# DS1302.net
KiCad netlist of a schematic drawn in Altium Designer
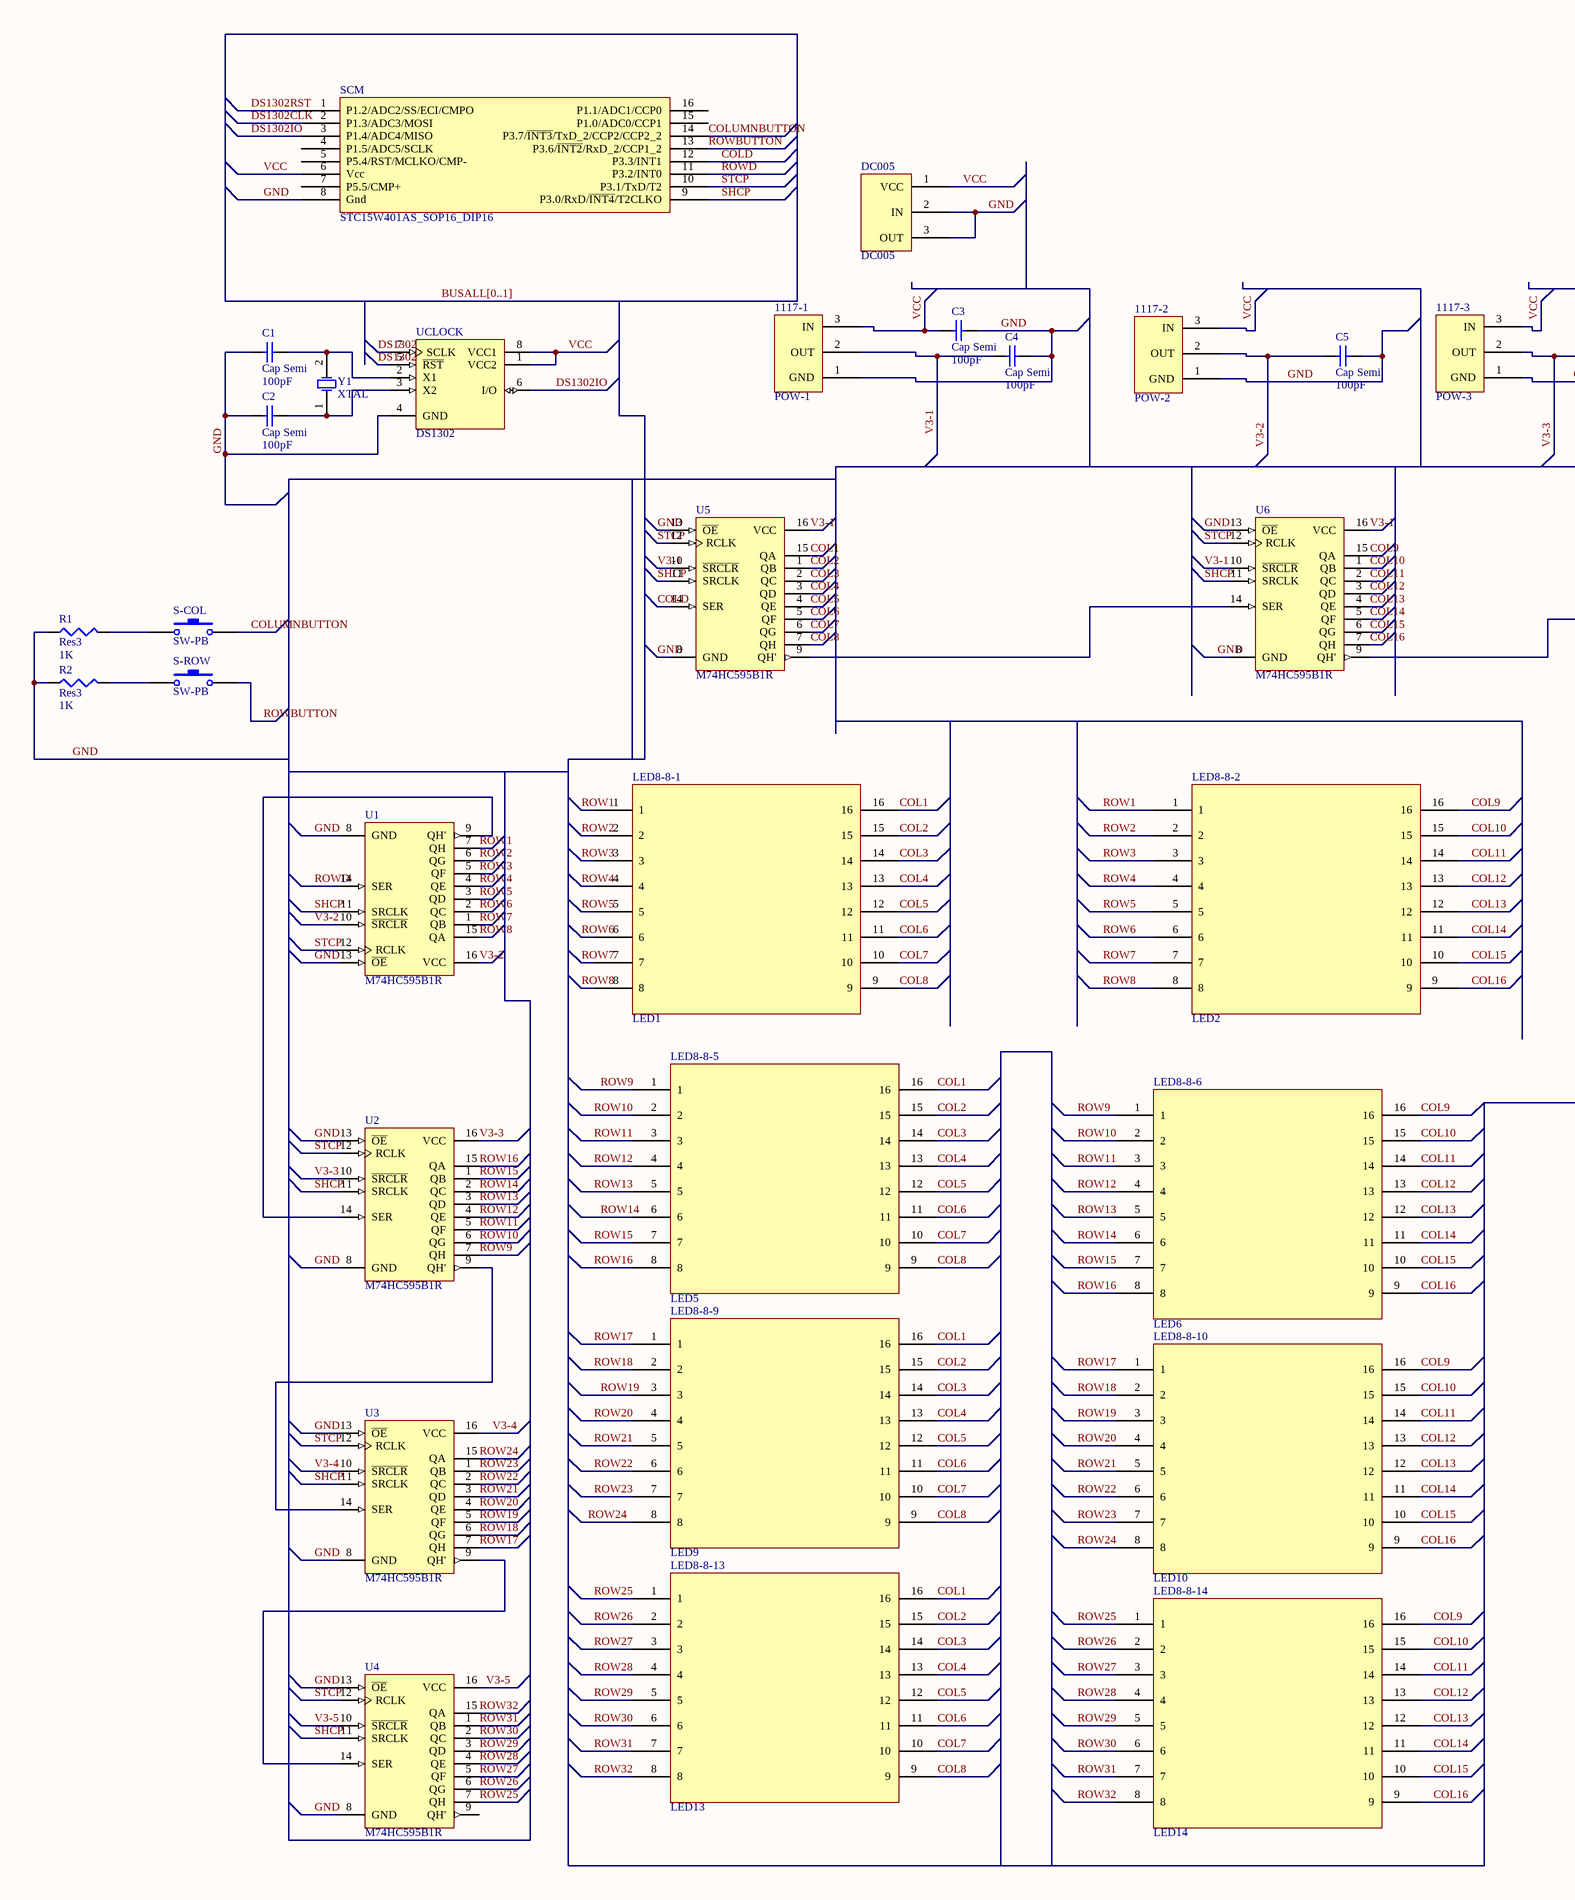
[diagram p0: DS1302.SchDoc, left]
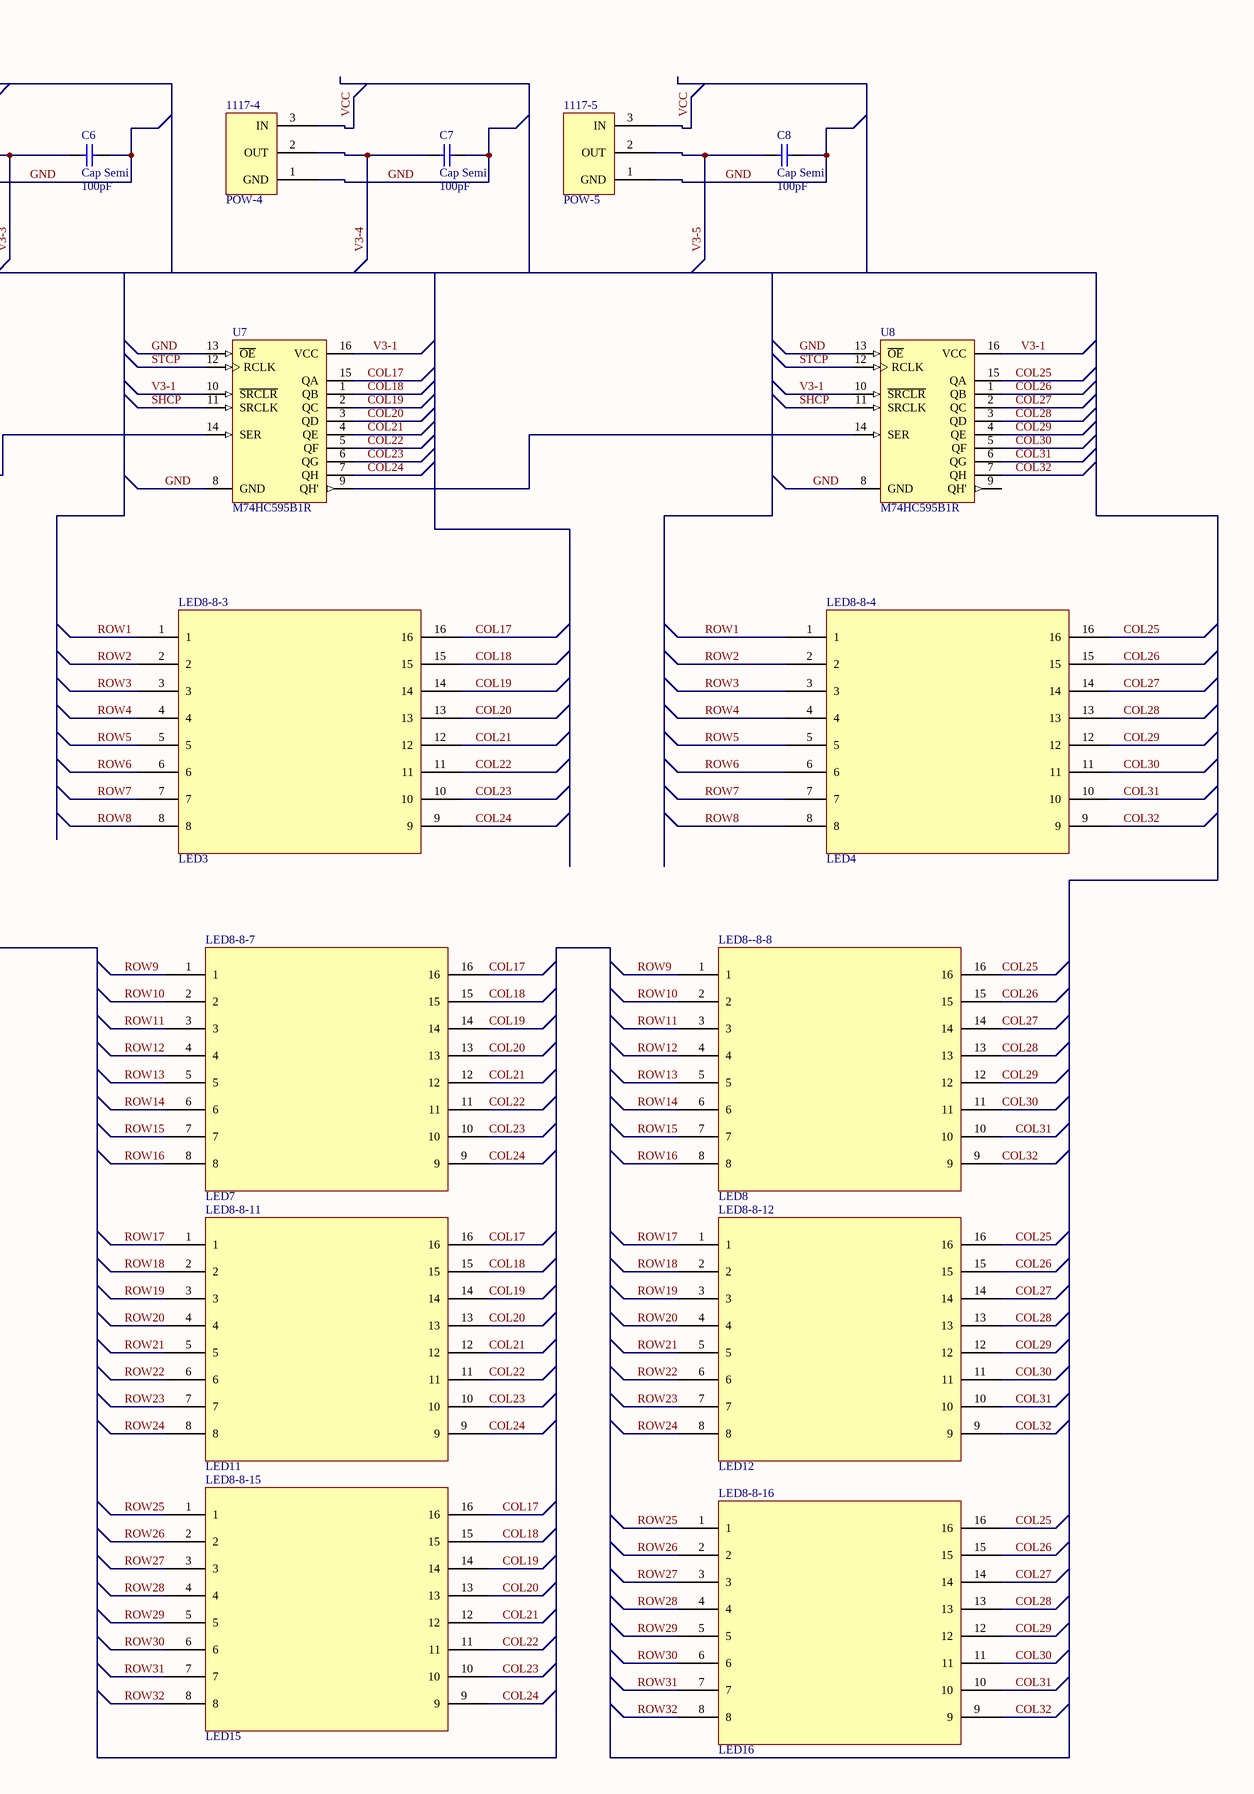
[diagram p1: DS1302.SchDoc, right]

(export (version "E")
  (design (tool "Eeschema 10.0.6"))
  (components
    (comp (ref "1117-1") (value "POW-1") (footprint "SOT223-4L") (libsource (lib "*") (part "1117")))
    (comp (ref "1117-2") (value "POW-2") (footprint "SOT223-4L") (libsource (lib "*") (part "1117")))
    (comp (ref "1117-3") (value "POW-3") (footprint "SOT223-4L") (libsource (lib "*") (part "1117")))
    (comp (ref "1117-4") (value "POW-4") (footprint "SOT223-4L") (libsource (lib "*") (part "1117")))
    (comp (ref "1117-5") (value "POW-5") (footprint "SOT223-4L") (libsource (lib "*") (part "1117")))
    (comp (ref "C1")
      (value "Cap Semi")
      (footprint "2012[0805]")
      (description "Capacitor (Semiconductor SIM Model)")
      (fields (field (name "ALTIUM_VALUE") "100pF") (field (name "PUBLISHER") "Altium Limited"))
      (libsource (lib "Miscellaneous Devices") (part "Cap Semi"))
    )
    (comp (ref "C2")
      (value "Cap Semi")
      (footprint "2012[0805]")
      (description "Capacitor (Semiconductor SIM Model)")
      (fields (field (name "ALTIUM_VALUE") "100pF") (field (name "PUBLISHER") "Altium Limited"))
      (libsource (lib "Miscellaneous Devices") (part "Cap Semi"))
    )
    (comp (ref "C3")
      (value "Cap Semi")
      (footprint "2012[0805]")
      (description "Capacitor (Semiconductor SIM Model)")
      (fields (field (name "ALTIUM_VALUE") "100pF") (field (name "PUBLISHER") "Altium Limited"))
      (libsource (lib "Miscellaneous Devices") (part "Cap Semi"))
    )
    (comp (ref "C4")
      (value "Cap Semi")
      (footprint "2012[0805]")
      (description "Capacitor (Semiconductor SIM Model)")
      (fields (field (name "ALTIUM_VALUE") "100pF") (field (name "PUBLISHER") "Altium Limited"))
      (libsource (lib "Miscellaneous Devices") (part "Cap Semi"))
    )
    (comp (ref "C5")
      (value "Cap Semi")
      (footprint "2012[0805]")
      (description "Capacitor (Semiconductor SIM Model)")
      (fields (field (name "ALTIUM_VALUE") "100pF") (field (name "PUBLISHER") "Altium Limited"))
      (libsource (lib "Miscellaneous Devices") (part "Cap Semi"))
    )
    (comp (ref "C6")
      (value "Cap Semi")
      (footprint "2012[0805]")
      (description "Capacitor (Semiconductor SIM Model)")
      (fields (field (name "ALTIUM_VALUE") "100pF") (field (name "PUBLISHER") "Altium Limited"))
      (libsource (lib "Miscellaneous Devices") (part "Cap Semi"))
    )
    (comp (ref "C7")
      (value "Cap Semi")
      (footprint "2012[0805]")
      (description "Capacitor (Semiconductor SIM Model)")
      (fields (field (name "ALTIUM_VALUE") "100pF") (field (name "PUBLISHER") "Altium Limited"))
      (libsource (lib "Miscellaneous Devices") (part "Cap Semi"))
    )
    (comp (ref "C8")
      (value "Cap Semi")
      (footprint "2012[0805]")
      (description "Capacitor (Semiconductor SIM Model)")
      (fields (field (name "ALTIUM_VALUE") "100pF") (field (name "PUBLISHER") "Altium Limited"))
      (libsource (lib "Miscellaneous Devices") (part "Cap Semi"))
    )
    (comp (ref "DC005") (value "DC005") (footprint "DC005") (libsource (lib "*") (part "DC005")))
    (comp (ref "LED8--8-8")
      (value "LED8")
      (footprint "LED8-8New")
      (libsource (lib "Schlib1") (part "LED8-8"))
    )
    (comp (ref "LED8-8-1") (value "LED1") (footprint "LED8-8New") (libsource (lib "Schlib1") (part "LED8-8")))
    (comp (ref "LED8-8-2") (value "LED2") (footprint "LED8-8New") (libsource (lib "") (part "LED8-8_1")))
    (comp (ref "LED8-8-3") (value "LED3") (footprint "LED8-8New") (libsource (lib "") (part "LED8-8_1")))
    (comp (ref "LED8-8-4") (value "LED4") (footprint "LED8-8New") (libsource (lib "") (part "LED8-8_1")))
    (comp (ref "LED8-8-5") (value "LED5") (footprint "LED8-8New") (libsource (lib "Schlib1") (part "LED8-8")))
    (comp (ref "LED8-8-6") (value "LED6") (footprint "LED8-8New") (libsource (lib "Schlib1") (part "LED8-8")))
    (comp (ref "LED8-8-7") (value "LED7") (footprint "LED8-8New") (libsource (lib "Schlib1") (part "LED8-8")))
    (comp (ref "LED8-8-9") (value "LED9") (footprint "LED8-8New") (libsource (lib "Schlib1") (part "LED8-8")))
    (comp (ref "LED8-8-10")
      (value "LED10")
      (footprint "LED8-8New")
      (libsource (lib "Schlib1") (part "LED8-8"))
    )
    (comp (ref "LED8-8-11")
      (value "LED11")
      (footprint "LED8-8New")
      (libsource (lib "Schlib1") (part "LED8-8"))
    )
    (comp (ref "LED8-8-12")
      (value "LED12")
      (footprint "LED8-8New")
      (libsource (lib "Schlib1") (part "LED8-8"))
    )
    (comp (ref "LED8-8-13") (value "LED13") (footprint "LED8-8New") (libsource (lib "") (part "LED8-8_1")))
    (comp (ref "LED8-8-14") (value "LED14") (footprint "LED8-8New") (libsource (lib "*") (part "LED8-8")))
    (comp (ref "LED8-8-15") (value "LED15") (footprint "LED8-8New") (libsource (lib "*") (part "LED8-8")))
    (comp (ref "LED8-8-16") (value "LED16") (footprint "LED8-8New") (libsource (lib "*") (part "LED8-8")))
    (comp (ref "R1")
      (value "Res3")
      (footprint "2012[0805]")
      (description "Resistor")
      (fields (field (name "ALTIUM_VALUE") "1K") (field (name "PUBLISHER") "Altium Limited"))
      (libsource (lib "Miscellaneous Devices") (part "Res3"))
    )
    (comp (ref "R2")
      (value "Res3")
      (footprint "2012[0805]")
      (description "Resistor")
      (fields (field (name "ALTIUM_VALUE") "1K") (field (name "PUBLISHER") "Altium Limited"))
      (libsource (lib "Miscellaneous Devices") (part "Res3"))
    )
    (comp (ref "S-COL")
      (value "SW-PB")
      (footprint "6332[2512]")
      (description "Switch")
      (fields (field (name "PUBLISHER") "Altium Limited"))
      (libsource (lib "Miscellaneous Devices") (part "SW-PB"))
    )
    (comp (ref "S-ROW")
      (value "SW-PB")
      (footprint "6332[2512]")
      (description "Switch")
      (fields (field (name "PUBLISHER") "Altium Limited"))
      (libsource (lib "Miscellaneous Devices") (part "SW-PB"))
    )
    (comp (ref "SCM")
      (value "STC15W401AS_SOP16_DIP16")
      (footprint "DIP-16")
      (libsource (lib "stcmcu_Protel99_sch") (part "STC15W401AS_SOP16_DIP16"))
    )
    (comp (ref "U1")
      (value "M74HC595B1R")
      (footprint "DIP-16")
      (description "8 Bit Shift Register with Output Latches (3 STATE)")
      (fields (field (name "PUBLISHER") "Altium Limited"))
      (libsource (lib "") (part "M74HC595B1R_1"))
    )
    (comp (ref "U2")
      (value "M74HC595B1R")
      (footprint "DIP-16")
      (description "8 Bit Shift Register with Output Latches (3 STATE)")
      (fields (field (name "PUBLISHER") "Altium Limited"))
      (libsource (lib "ST Logic Register") (part "M74HC595B1R"))
    )
    (comp (ref "U3")
      (value "M74HC595B1R")
      (footprint "DIP-16")
      (description "8 Bit Shift Register with Output Latches (3 STATE)")
      (fields (field (name "PUBLISHER") "Altium Limited"))
      (libsource (lib "ST Logic Register") (part "M74HC595B1R"))
    )
    (comp (ref "U4")
      (value "M74HC595B1R")
      (footprint "DIP-16")
      (description "8 Bit Shift Register with Output Latches (3 STATE)")
      (fields (field (name "PUBLISHER") "Altium Limited"))
      (libsource (lib "ST Logic Register") (part "M74HC595B1R"))
    )
    (comp (ref "U5")
      (value "M74HC595B1R")
      (footprint "DIP-16")
      (description "8 Bit Shift Register with Output Latches (3 STATE)")
      (fields (field (name "PUBLISHER") "Altium Limited"))
      (libsource (lib "ST Logic Register") (part "M74HC595B1R"))
    )
    (comp (ref "U6")
      (value "M74HC595B1R")
      (footprint "DIP-16")
      (description "8 Bit Shift Register with Output Latches (3 STATE)")
      (fields (field (name "PUBLISHER") "Altium Limited"))
      (libsource (lib "ST Logic Register") (part "M74HC595B1R"))
    )
    (comp (ref "U7")
      (value "M74HC595B1R")
      (footprint "DIP-16")
      (description "8 Bit Shift Register with Output Latches (3 STATE)")
      (fields (field (name "PUBLISHER") "Altium Limited"))
      (libsource (lib "ST Logic Register") (part "M74HC595B1R"))
    )
    (comp (ref "U8")
      (value "M74HC595B1R")
      (footprint "DIP-16")
      (description "8 Bit Shift Register with Output Latches (3 STATE)")
      (fields (field (name "PUBLISHER") "Altium Limited"))
      (libsource (lib "ST Logic Register") (part "M74HC595B1R"))
    )
    (comp (ref "UCLOCK")
      (value "DS1302")
      (footprint "DIP8")
      (description "Trickle Charge Timekeeping Chip")
      (fields (field (name "PUBLISHER") "Altium Limited"))
      (libsource (lib "Dallas Peripheral Real Time Clock") (part "DS1302"))
    )
    (comp (ref "Y1")
      (value "XTAL")
      (footprint "R38")
      (description "Crystal Oscillator")
      (fields (field (name "PUBLISHER") "Altium Limited"))
      (libsource (lib "Miscellaneous Devices") (part "XTAL"))
    )
  )
  (nets
    (net (code "4") (name "/COL1") (class "Default")
      (node (ref "LED8-8-1") (pin "16") (pinfunction "16_16") (pintype "passive"))
      (node (ref "LED8-8-13") (pin "16") (pinfunction "16_16") (pintype "passive"))
      (node (ref "LED8-8-5") (pin "16") (pinfunction "16_16") (pintype "passive"))
      (node (ref "LED8-8-9") (pin "16") (pinfunction "16_16") (pintype "passive"))
      (node (ref "U5") (pin "15") (pinfunction "QA_15") (pintype "tri_state"))
    )
    (net (code "5") (name "/COL2") (class "Default")
      (node (ref "LED8-8-1") (pin "15") (pinfunction "15_15") (pintype "passive"))
      (node (ref "LED8-8-13") (pin "15") (pinfunction "15_15") (pintype "passive"))
      (node (ref "LED8-8-5") (pin "15") (pinfunction "15_15") (pintype "passive"))
      (node (ref "LED8-8-9") (pin "15") (pinfunction "15_15") (pintype "passive"))
      (node (ref "U5") (pin "1") (pinfunction "QB_1") (pintype "tri_state"))
    )
    (net (code "6") (name "/COL3") (class "Default")
      (node (ref "LED8-8-1") (pin "14") (pinfunction "14_14") (pintype "passive"))
      (node (ref "LED8-8-13") (pin "14") (pinfunction "14_14") (pintype "passive"))
      (node (ref "LED8-8-5") (pin "14") (pinfunction "14_14") (pintype "passive"))
      (node (ref "LED8-8-9") (pin "14") (pinfunction "14_14") (pintype "passive"))
      (node (ref "U5") (pin "2") (pinfunction "QC_2") (pintype "tri_state"))
    )
    (net (code "7") (name "/COL4") (class "Default")
      (node (ref "LED8-8-1") (pin "13") (pinfunction "13_13") (pintype "passive"))
      (node (ref "LED8-8-13") (pin "13") (pinfunction "13_13") (pintype "passive"))
      (node (ref "LED8-8-5") (pin "13") (pinfunction "13_13") (pintype "passive"))
      (node (ref "LED8-8-9") (pin "13") (pinfunction "13_13") (pintype "passive"))
      (node (ref "U5") (pin "3") (pinfunction "QD_3") (pintype "tri_state"))
    )
    (net (code "8") (name "/COL5") (class "Default")
      (node (ref "LED8-8-1") (pin "12") (pinfunction "12_12") (pintype "passive"))
      (node (ref "LED8-8-13") (pin "12") (pinfunction "12_12") (pintype "passive"))
      (node (ref "LED8-8-5") (pin "12") (pinfunction "12_12") (pintype "passive"))
      (node (ref "LED8-8-9") (pin "12") (pinfunction "12_12") (pintype "passive"))
      (node (ref "U5") (pin "4") (pinfunction "QE_4") (pintype "tri_state"))
    )
    (net (code "9") (name "/COL6") (class "Default")
      (node (ref "LED8-8-1") (pin "11") (pinfunction "11_11") (pintype "passive"))
      (node (ref "LED8-8-13") (pin "11") (pinfunction "11_11") (pintype "passive"))
      (node (ref "LED8-8-5") (pin "11") (pinfunction "11_11") (pintype "passive"))
      (node (ref "LED8-8-9") (pin "11") (pinfunction "11_11") (pintype "passive"))
      (node (ref "U5") (pin "5") (pinfunction "QF_5") (pintype "tri_state"))
    )
    (net (code "10") (name "/COL7") (class "Default")
      (node (ref "LED8-8-1") (pin "10") (pinfunction "10_10") (pintype "passive"))
      (node (ref "LED8-8-13") (pin "10") (pinfunction "10_10") (pintype "passive"))
      (node (ref "LED8-8-5") (pin "10") (pinfunction "10_10") (pintype "passive"))
      (node (ref "LED8-8-9") (pin "10") (pinfunction "10_10") (pintype "passive"))
      (node (ref "U5") (pin "6") (pinfunction "QG_6") (pintype "tri_state"))
    )
    (net (code "11") (name "/COL8") (class "Default")
      (node (ref "LED8-8-1") (pin "9") (pinfunction "9_9") (pintype "passive"))
      (node (ref "LED8-8-13") (pin "9") (pinfunction "9_9") (pintype "passive"))
      (node (ref "LED8-8-5") (pin "9") (pinfunction "9_9") (pintype "passive"))
      (node (ref "LED8-8-9") (pin "9") (pinfunction "9_9") (pintype "passive"))
      (node (ref "U5") (pin "7") (pinfunction "QH_7") (pintype "tri_state"))
    )
    (net (code "12") (name "/COL9") (class "Default")
      (node (ref "LED8-8-10") (pin "16") (pinfunction "16_16") (pintype "passive"))
      (node (ref "LED8-8-14") (pin "16") (pinfunction "16_16") (pintype "passive"))
      (node (ref "LED8-8-2") (pin "16") (pinfunction "16_16") (pintype "passive"))
      (node (ref "LED8-8-6") (pin "16") (pinfunction "16_16") (pintype "passive"))
      (node (ref "U6") (pin "15") (pinfunction "QA_15") (pintype "tri_state"))
    )
    (net (code "13") (name "/COL10") (class "Default")
      (node (ref "LED8-8-10") (pin "15") (pinfunction "15_15") (pintype "passive"))
      (node (ref "LED8-8-14") (pin "15") (pinfunction "15_15") (pintype "passive"))
      (node (ref "LED8-8-2") (pin "15") (pinfunction "15_15") (pintype "passive"))
      (node (ref "LED8-8-6") (pin "15") (pinfunction "15_15") (pintype "passive"))
      (node (ref "U6") (pin "1") (pinfunction "QB_1") (pintype "tri_state"))
    )
    (net (code "14") (name "/COL11") (class "Default")
      (node (ref "LED8-8-10") (pin "14") (pinfunction "14_14") (pintype "passive"))
      (node (ref "LED8-8-14") (pin "14") (pinfunction "14_14") (pintype "passive"))
      (node (ref "LED8-8-2") (pin "14") (pinfunction "14_14") (pintype "passive"))
      (node (ref "LED8-8-6") (pin "14") (pinfunction "14_14") (pintype "passive"))
      (node (ref "U6") (pin "2") (pinfunction "QC_2") (pintype "tri_state"))
    )
    (net (code "15") (name "/COL12") (class "Default")
      (node (ref "LED8-8-10") (pin "13") (pinfunction "13_13") (pintype "passive"))
      (node (ref "LED8-8-14") (pin "13") (pinfunction "13_13") (pintype "passive"))
      (node (ref "LED8-8-2") (pin "13") (pinfunction "13_13") (pintype "passive"))
      (node (ref "LED8-8-6") (pin "13") (pinfunction "13_13") (pintype "passive"))
      (node (ref "U6") (pin "3") (pinfunction "QD_3") (pintype "tri_state"))
    )
    (net (code "16") (name "/COL13") (class "Default")
      (node (ref "LED8-8-10") (pin "12") (pinfunction "12_12") (pintype "passive"))
      (node (ref "LED8-8-14") (pin "12") (pinfunction "12_12") (pintype "passive"))
      (node (ref "LED8-8-2") (pin "12") (pinfunction "12_12") (pintype "passive"))
      (node (ref "LED8-8-6") (pin "12") (pinfunction "12_12") (pintype "passive"))
      (node (ref "U6") (pin "4") (pinfunction "QE_4") (pintype "tri_state"))
    )
    (net (code "17") (name "/COL14") (class "Default")
      (node (ref "LED8-8-10") (pin "11") (pinfunction "11_11") (pintype "passive"))
      (node (ref "LED8-8-14") (pin "11") (pinfunction "11_11") (pintype "passive"))
      (node (ref "LED8-8-2") (pin "11") (pinfunction "11_11") (pintype "passive"))
      (node (ref "LED8-8-6") (pin "11") (pinfunction "11_11") (pintype "passive"))
      (node (ref "U6") (pin "5") (pinfunction "QF_5") (pintype "tri_state"))
    )
    (net (code "18") (name "/COL15") (class "Default")
      (node (ref "LED8-8-10") (pin "10") (pinfunction "10_10") (pintype "passive"))
      (node (ref "LED8-8-14") (pin "10") (pinfunction "10_10") (pintype "passive"))
      (node (ref "LED8-8-2") (pin "10") (pinfunction "10_10") (pintype "passive"))
      (node (ref "LED8-8-6") (pin "10") (pinfunction "10_10") (pintype "passive"))
      (node (ref "U6") (pin "6") (pinfunction "QG_6") (pintype "tri_state"))
    )
    (net (code "19") (name "/COL16") (class "Default")
      (node (ref "LED8-8-10") (pin "9") (pinfunction "9_9") (pintype "passive"))
      (node (ref "LED8-8-14") (pin "9") (pinfunction "9_9") (pintype "passive"))
      (node (ref "LED8-8-2") (pin "9") (pinfunction "9_9") (pintype "passive"))
      (node (ref "LED8-8-6") (pin "9") (pinfunction "9_9") (pintype "passive"))
      (node (ref "U6") (pin "7") (pinfunction "QH_7") (pintype "tri_state"))
    )
    (net (code "20") (name "/COL17") (class "Default")
      (node (ref "LED8-8-11") (pin "16") (pinfunction "16_16") (pintype "passive"))
      (node (ref "LED8-8-15") (pin "16") (pinfunction "16_16") (pintype "passive"))
      (node (ref "LED8-8-3") (pin "16") (pinfunction "16_16") (pintype "passive"))
      (node (ref "LED8-8-7") (pin "16") (pinfunction "16_16") (pintype "passive"))
      (node (ref "U7") (pin "15") (pinfunction "QA_15") (pintype "tri_state"))
    )
    (net (code "21") (name "/COL18") (class "Default")
      (node (ref "LED8-8-11") (pin "15") (pinfunction "15_15") (pintype "passive"))
      (node (ref "LED8-8-15") (pin "15") (pinfunction "15_15") (pintype "passive"))
      (node (ref "LED8-8-3") (pin "15") (pinfunction "15_15") (pintype "passive"))
      (node (ref "LED8-8-7") (pin "15") (pinfunction "15_15") (pintype "passive"))
      (node (ref "U7") (pin "1") (pinfunction "QB_1") (pintype "tri_state"))
    )
    (net (code "22") (name "/COL19") (class "Default")
      (node (ref "LED8-8-11") (pin "14") (pinfunction "14_14") (pintype "passive"))
      (node (ref "LED8-8-15") (pin "14") (pinfunction "14_14") (pintype "passive"))
      (node (ref "LED8-8-3") (pin "14") (pinfunction "14_14") (pintype "passive"))
      (node (ref "LED8-8-7") (pin "14") (pinfunction "14_14") (pintype "passive"))
      (node (ref "U7") (pin "2") (pinfunction "QC_2") (pintype "tri_state"))
    )
    (net (code "23") (name "/COL20") (class "Default")
      (node (ref "LED8-8-11") (pin "13") (pinfunction "13_13") (pintype "passive"))
      (node (ref "LED8-8-15") (pin "13") (pinfunction "13_13") (pintype "passive"))
      (node (ref "LED8-8-3") (pin "13") (pinfunction "13_13") (pintype "passive"))
      (node (ref "LED8-8-7") (pin "13") (pinfunction "13_13") (pintype "passive"))
      (node (ref "U7") (pin "3") (pinfunction "QD_3") (pintype "tri_state"))
    )
    (net (code "24") (name "/COL21") (class "Default")
      (node (ref "LED8-8-11") (pin "12") (pinfunction "12_12") (pintype "passive"))
      (node (ref "LED8-8-15") (pin "12") (pinfunction "12_12") (pintype "passive"))
      (node (ref "LED8-8-3") (pin "12") (pinfunction "12_12") (pintype "passive"))
      (node (ref "LED8-8-7") (pin "12") (pinfunction "12_12") (pintype "passive"))
      (node (ref "U7") (pin "4") (pinfunction "QE_4") (pintype "tri_state"))
    )
    (net (code "25") (name "/COL22") (class "Default")
      (node (ref "LED8-8-11") (pin "11") (pinfunction "11_11") (pintype "passive"))
      (node (ref "LED8-8-15") (pin "11") (pinfunction "11_11") (pintype "passive"))
      (node (ref "LED8-8-3") (pin "11") (pinfunction "11_11") (pintype "passive"))
      (node (ref "LED8-8-7") (pin "11") (pinfunction "11_11") (pintype "passive"))
      (node (ref "U7") (pin "5") (pinfunction "QF_5") (pintype "tri_state"))
    )
    (net (code "26") (name "/COL23") (class "Default")
      (node (ref "LED8-8-11") (pin "10") (pinfunction "10_10") (pintype "passive"))
      (node (ref "LED8-8-15") (pin "10") (pinfunction "10_10") (pintype "passive"))
      (node (ref "LED8-8-3") (pin "10") (pinfunction "10_10") (pintype "passive"))
      (node (ref "LED8-8-7") (pin "10") (pinfunction "10_10") (pintype "passive"))
      (node (ref "U7") (pin "6") (pinfunction "QG_6") (pintype "tri_state"))
    )
    (net (code "27") (name "/COL24") (class "Default")
      (node (ref "LED8-8-11") (pin "9") (pinfunction "9_9") (pintype "passive"))
      (node (ref "LED8-8-15") (pin "9") (pinfunction "9_9") (pintype "passive"))
      (node (ref "LED8-8-3") (pin "9") (pinfunction "9_9") (pintype "passive"))
      (node (ref "LED8-8-7") (pin "9") (pinfunction "9_9") (pintype "passive"))
      (node (ref "U7") (pin "7") (pinfunction "QH_7") (pintype "tri_state"))
    )
    (net (code "28") (name "/COL25") (class "Default")
      (node (ref "LED8--8-8") (pin "16") (pinfunction "16_16") (pintype "passive"))
      (node (ref "LED8-8-12") (pin "16") (pinfunction "16_16") (pintype "passive"))
      (node (ref "LED8-8-16") (pin "16") (pinfunction "16_16") (pintype "passive"))
      (node (ref "LED8-8-4") (pin "16") (pinfunction "16_16") (pintype "passive"))
      (node (ref "U8") (pin "15") (pinfunction "QA_15") (pintype "tri_state"))
    )
    (net (code "29") (name "/COL26") (class "Default")
      (node (ref "LED8--8-8") (pin "15") (pinfunction "15_15") (pintype "passive"))
      (node (ref "LED8-8-12") (pin "15") (pinfunction "15_15") (pintype "passive"))
      (node (ref "LED8-8-16") (pin "15") (pinfunction "15_15") (pintype "passive"))
      (node (ref "LED8-8-4") (pin "15") (pinfunction "15_15") (pintype "passive"))
      (node (ref "U8") (pin "1") (pinfunction "QB_1") (pintype "tri_state"))
    )
    (net (code "30") (name "/COL27") (class "Default")
      (node (ref "LED8--8-8") (pin "14") (pinfunction "14_14") (pintype "passive"))
      (node (ref "LED8-8-12") (pin "14") (pinfunction "14_14") (pintype "passive"))
      (node (ref "LED8-8-16") (pin "14") (pinfunction "14_14") (pintype "passive"))
      (node (ref "LED8-8-4") (pin "14") (pinfunction "14_14") (pintype "passive"))
      (node (ref "U8") (pin "2") (pinfunction "QC_2") (pintype "tri_state"))
    )
    (net (code "31") (name "/COL28") (class "Default")
      (node (ref "LED8--8-8") (pin "13") (pinfunction "13_13") (pintype "passive"))
      (node (ref "LED8-8-12") (pin "13") (pinfunction "13_13") (pintype "passive"))
      (node (ref "LED8-8-16") (pin "13") (pinfunction "13_13") (pintype "passive"))
      (node (ref "LED8-8-4") (pin "13") (pinfunction "13_13") (pintype "passive"))
      (node (ref "U8") (pin "3") (pinfunction "QD_3") (pintype "tri_state"))
    )
    (net (code "32") (name "/COL29") (class "Default")
      (node (ref "LED8--8-8") (pin "12") (pinfunction "12_12") (pintype "passive"))
      (node (ref "LED8-8-12") (pin "12") (pinfunction "12_12") (pintype "passive"))
      (node (ref "LED8-8-16") (pin "12") (pinfunction "12_12") (pintype "passive"))
      (node (ref "LED8-8-4") (pin "12") (pinfunction "12_12") (pintype "passive"))
      (node (ref "U8") (pin "4") (pinfunction "QE_4") (pintype "tri_state"))
    )
    (net (code "33") (name "/COL30") (class "Default")
      (node (ref "LED8--8-8") (pin "11") (pinfunction "11_11") (pintype "passive"))
      (node (ref "LED8-8-12") (pin "11") (pinfunction "11_11") (pintype "passive"))
      (node (ref "LED8-8-16") (pin "11") (pinfunction "11_11") (pintype "passive"))
      (node (ref "LED8-8-4") (pin "11") (pinfunction "11_11") (pintype "passive"))
      (node (ref "U8") (pin "5") (pinfunction "QF_5") (pintype "tri_state"))
    )
    (net (code "34") (name "/COL31") (class "Default")
      (node (ref "LED8--8-8") (pin "10") (pinfunction "10_10") (pintype "passive"))
      (node (ref "LED8-8-12") (pin "10") (pinfunction "10_10") (pintype "passive"))
      (node (ref "LED8-8-16") (pin "10") (pinfunction "10_10") (pintype "passive"))
      (node (ref "LED8-8-4") (pin "10") (pinfunction "10_10") (pintype "passive"))
      (node (ref "U8") (pin "6") (pinfunction "QG_6") (pintype "tri_state"))
    )
    (net (code "35") (name "/COL32") (class "Default")
      (node (ref "LED8--8-8") (pin "9") (pinfunction "9_9") (pintype "passive"))
      (node (ref "LED8-8-12") (pin "9") (pinfunction "9_9") (pintype "passive"))
      (node (ref "LED8-8-16") (pin "9") (pinfunction "9_9") (pintype "passive"))
      (node (ref "LED8-8-4") (pin "9") (pinfunction "9_9") (pintype "passive"))
      (node (ref "U8") (pin "7") (pinfunction "QH_7") (pintype "tri_state"))
    )
    (net (code "36") (name "/COLD") (class "Default")
      (node (ref "SCM") (pin "12") (pinfunction "P3.3/INT1_12") (pintype "passive"))
      (node (ref "U5") (pin "14") (pinfunction "SER_14") (pintype "input"))
    )
    (net (code "37") (name "/COLUMNBUTTON") (class "Default")
      (node (ref "S-COL") (pin "2") (pinfunction "2_2") (pintype "passive"))
      (node (ref "SCM") (pin "14") (pinfunction "P3.7/~{INT3}/TxD_2/CCP2/CCP2_2_14") (pintype "passive"))
    )
    (net (code "38") (name "/DS1302CLK") (class "Default")
      (node (ref "SCM") (pin "2") (pinfunction "P1.3/ADC3/MOSI_2") (pintype "passive"))
      (node (ref "UCLOCK") (pin "7") (pinfunction "SCLK_7") (pintype "input"))
    )
    (net (code "39") (name "/DS1302IO") (class "Default")
      (node (ref "SCM") (pin "3") (pinfunction "P1.4/ADC4/MISO_3") (pintype "passive"))
      (node (ref "UCLOCK") (pin "6") (pinfunction "I/O_6") (pintype "bidirectional"))
    )
    (net (code "40") (name "/DS1302RST") (class "Default")
      (node (ref "SCM") (pin "1") (pinfunction "P1.2/ADC2/SS/ECI/CMPO_1") (pintype "passive"))
      (node (ref "UCLOCK") (pin "5") (pinfunction "~{RST}_5") (pintype "input"))
    )
    (net (code "41") (name "/GND") (class "Default")
      (node (ref "1117-1") (pin "1") (pinfunction "GND_1") (pintype "passive"))
      (node (ref "1117-2") (pin "1") (pinfunction "GND_1") (pintype "passive"))
      (node (ref "1117-3") (pin "1") (pinfunction "GND_1") (pintype "passive"))
      (node (ref "1117-4") (pin "1") (pinfunction "GND_1") (pintype "passive"))
      (node (ref "1117-5") (pin "1") (pinfunction "GND_1") (pintype "passive"))
      (node (ref "C1") (pin "1") (pinfunction "1_1") (pintype "passive"))
      (node (ref "C2") (pin "1") (pinfunction "1_1") (pintype "passive"))
      (node (ref "C3") (pin "2") (pinfunction "2_2") (pintype "passive"))
      (node (ref "C4") (pin "2") (pinfunction "2_2") (pintype "passive"))
      (node (ref "C5") (pin "2") (pinfunction "2_2") (pintype "passive"))
      (node (ref "C6") (pin "2") (pinfunction "2_2") (pintype "passive"))
      (node (ref "C7") (pin "2") (pinfunction "2_2") (pintype "passive"))
      (node (ref "C8") (pin "2") (pinfunction "2_2") (pintype "passive"))
      (node (ref "DC005") (pin "2") (pinfunction "IN_2") (pintype "passive"))
      (node (ref "DC005") (pin "3") (pinfunction "OUT_3") (pintype "passive"))
      (node (ref "R1") (pin "1") (pinfunction "1_1") (pintype "passive"))
      (node (ref "R2") (pin "1") (pinfunction "1_1") (pintype "passive"))
      (node (ref "SCM") (pin "8") (pinfunction "Gnd_8") (pintype "passive"))
      (node (ref "U1") (pin "13") (pinfunction "~{OE}_13") (pintype "input"))
      (node (ref "U1") (pin "8") (pinfunction "GND_8") (pintype "power_in"))
      (node (ref "U2") (pin "13") (pinfunction "~{OE}_13") (pintype "input"))
      (node (ref "U2") (pin "8") (pinfunction "GND_8") (pintype "power_in"))
      (node (ref "U3") (pin "13") (pinfunction "~{OE}_13") (pintype "input"))
      (node (ref "U3") (pin "8") (pinfunction "GND_8") (pintype "power_in"))
      (node (ref "U4") (pin "13") (pinfunction "~{OE}_13") (pintype "input"))
      (node (ref "U4") (pin "8") (pinfunction "GND_8") (pintype "power_in"))
      (node (ref "U5") (pin "13") (pinfunction "~{OE}_13") (pintype "input"))
      (node (ref "U5") (pin "8") (pinfunction "GND_8") (pintype "power_in"))
      (node (ref "U6") (pin "13") (pinfunction "~{OE}_13") (pintype "input"))
      (node (ref "U6") (pin "8") (pinfunction "GND_8") (pintype "power_in"))
      (node (ref "U7") (pin "13") (pinfunction "~{OE}_13") (pintype "input"))
      (node (ref "U7") (pin "8") (pinfunction "GND_8") (pintype "power_in"))
      (node (ref "U8") (pin "13") (pinfunction "~{OE}_13") (pintype "input"))
      (node (ref "U8") (pin "8") (pinfunction "GND_8") (pintype "power_in"))
      (node (ref "UCLOCK") (pin "4") (pinfunction "GND_4") (pintype "power_in"))
    )
    (net (code "42") (name "/ROW1") (class "Default")
      (node (ref "LED8-8-1") (pin "1") (pinfunction "1_1") (pintype "passive"))
      (node (ref "LED8-8-2") (pin "1") (pinfunction "1_1") (pintype "passive"))
      (node (ref "LED8-8-3") (pin "1") (pinfunction "1_1") (pintype "passive"))
      (node (ref "LED8-8-4") (pin "1") (pinfunction "1_1") (pintype "passive"))
      (node (ref "U1") (pin "7") (pinfunction "QH_7") (pintype "tri_state"))
    )
    (net (code "43") (name "/ROW2") (class "Default")
      (node (ref "LED8-8-1") (pin "2") (pinfunction "2_2") (pintype "passive"))
      (node (ref "LED8-8-2") (pin "2") (pinfunction "2_2") (pintype "passive"))
      (node (ref "LED8-8-3") (pin "2") (pinfunction "2_2") (pintype "passive"))
      (node (ref "LED8-8-4") (pin "2") (pinfunction "2_2") (pintype "passive"))
      (node (ref "U1") (pin "6") (pinfunction "QG_6") (pintype "tri_state"))
    )
    (net (code "44") (name "/ROW3") (class "Default")
      (node (ref "LED8-8-1") (pin "3") (pinfunction "3_3") (pintype "passive"))
      (node (ref "LED8-8-2") (pin "3") (pinfunction "3_3") (pintype "passive"))
      (node (ref "LED8-8-3") (pin "3") (pinfunction "3_3") (pintype "passive"))
      (node (ref "LED8-8-4") (pin "3") (pinfunction "3_3") (pintype "passive"))
      (node (ref "U1") (pin "5") (pinfunction "QF_5") (pintype "tri_state"))
    )
    (net (code "45") (name "/ROW4") (class "Default")
      (node (ref "LED8-8-1") (pin "4") (pinfunction "4_4") (pintype "passive"))
      (node (ref "LED8-8-2") (pin "4") (pinfunction "4_4") (pintype "passive"))
      (node (ref "LED8-8-3") (pin "4") (pinfunction "4_4") (pintype "passive"))
      (node (ref "LED8-8-4") (pin "4") (pinfunction "4_4") (pintype "passive"))
      (node (ref "U1") (pin "4") (pinfunction "QE_4") (pintype "tri_state"))
    )
    (net (code "46") (name "/ROW5") (class "Default")
      (node (ref "LED8-8-1") (pin "5") (pinfunction "5_5") (pintype "passive"))
      (node (ref "LED8-8-2") (pin "5") (pinfunction "5_5") (pintype "passive"))
      (node (ref "LED8-8-3") (pin "5") (pinfunction "5_5") (pintype "passive"))
      (node (ref "LED8-8-4") (pin "5") (pinfunction "5_5") (pintype "passive"))
      (node (ref "U1") (pin "3") (pinfunction "QD_3") (pintype "tri_state"))
    )
    (net (code "47") (name "/ROW6") (class "Default")
      (node (ref "LED8-8-1") (pin "6") (pinfunction "6_6") (pintype "passive"))
      (node (ref "LED8-8-2") (pin "6") (pinfunction "6_6") (pintype "passive"))
      (node (ref "LED8-8-3") (pin "6") (pinfunction "6_6") (pintype "passive"))
      (node (ref "LED8-8-4") (pin "6") (pinfunction "6_6") (pintype "passive"))
      (node (ref "U1") (pin "2") (pinfunction "QC_2") (pintype "tri_state"))
    )
    (net (code "48") (name "/ROW7") (class "Default")
      (node (ref "LED8-8-1") (pin "7") (pinfunction "7_7") (pintype "passive"))
      (node (ref "LED8-8-2") (pin "7") (pinfunction "7_7") (pintype "passive"))
      (node (ref "LED8-8-3") (pin "7") (pinfunction "7_7") (pintype "passive"))
      (node (ref "LED8-8-4") (pin "7") (pinfunction "7_7") (pintype "passive"))
      (node (ref "U1") (pin "1") (pinfunction "QB_1") (pintype "tri_state"))
    )
    (net (code "49") (name "/ROW8") (class "Default")
      (node (ref "LED8-8-1") (pin "8") (pinfunction "8_8") (pintype "passive"))
      (node (ref "LED8-8-2") (pin "8") (pinfunction "8_8") (pintype "passive"))
      (node (ref "LED8-8-3") (pin "8") (pinfunction "8_8") (pintype "passive"))
      (node (ref "LED8-8-4") (pin "8") (pinfunction "8_8") (pintype "passive"))
      (node (ref "U1") (pin "15") (pinfunction "QA_15") (pintype "tri_state"))
    )
    (net (code "50") (name "/ROW9") (class "Default")
      (node (ref "LED8--8-8") (pin "1") (pinfunction "1_1") (pintype "passive"))
      (node (ref "LED8-8-5") (pin "1") (pinfunction "1_1") (pintype "passive"))
      (node (ref "LED8-8-6") (pin "1") (pinfunction "1_1") (pintype "passive"))
      (node (ref "LED8-8-7") (pin "1") (pinfunction "1_1") (pintype "passive"))
      (node (ref "U2") (pin "7") (pinfunction "QH_7") (pintype "tri_state"))
    )
    (net (code "51") (name "/ROW10") (class "Default")
      (node (ref "LED8--8-8") (pin "2") (pinfunction "2_2") (pintype "passive"))
      (node (ref "LED8-8-5") (pin "2") (pinfunction "2_2") (pintype "passive"))
      (node (ref "LED8-8-6") (pin "2") (pinfunction "2_2") (pintype "passive"))
      (node (ref "LED8-8-7") (pin "2") (pinfunction "2_2") (pintype "passive"))
      (node (ref "U2") (pin "6") (pinfunction "QG_6") (pintype "tri_state"))
    )
    (net (code "52") (name "/ROW11") (class "Default")
      (node (ref "LED8--8-8") (pin "3") (pinfunction "3_3") (pintype "passive"))
      (node (ref "LED8-8-5") (pin "3") (pinfunction "3_3") (pintype "passive"))
      (node (ref "LED8-8-6") (pin "3") (pinfunction "3_3") (pintype "passive"))
      (node (ref "LED8-8-7") (pin "3") (pinfunction "3_3") (pintype "passive"))
      (node (ref "U2") (pin "5") (pinfunction "QF_5") (pintype "tri_state"))
    )
    (net (code "53") (name "/ROW12") (class "Default")
      (node (ref "LED8--8-8") (pin "4") (pinfunction "4_4") (pintype "passive"))
      (node (ref "LED8-8-5") (pin "4") (pinfunction "4_4") (pintype "passive"))
      (node (ref "LED8-8-6") (pin "4") (pinfunction "4_4") (pintype "passive"))
      (node (ref "LED8-8-7") (pin "4") (pinfunction "4_4") (pintype "passive"))
      (node (ref "U2") (pin "4") (pinfunction "QE_4") (pintype "tri_state"))
    )
    (net (code "54") (name "/ROW13") (class "Default")
      (node (ref "LED8--8-8") (pin "5") (pinfunction "5_5") (pintype "passive"))
      (node (ref "LED8-8-5") (pin "5") (pinfunction "5_5") (pintype "passive"))
      (node (ref "LED8-8-6") (pin "5") (pinfunction "5_5") (pintype "passive"))
      (node (ref "LED8-8-7") (pin "5") (pinfunction "5_5") (pintype "passive"))
      (node (ref "U2") (pin "3") (pinfunction "QD_3") (pintype "tri_state"))
    )
    (net (code "55") (name "/ROW14") (class "Default")
      (node (ref "LED8--8-8") (pin "6") (pinfunction "6_6") (pintype "passive"))
      (node (ref "LED8-8-5") (pin "6") (pinfunction "6_6") (pintype "passive"))
      (node (ref "LED8-8-6") (pin "6") (pinfunction "6_6") (pintype "passive"))
      (node (ref "LED8-8-7") (pin "6") (pinfunction "6_6") (pintype "passive"))
      (node (ref "U2") (pin "2") (pinfunction "QC_2") (pintype "tri_state"))
    )
    (net (code "56") (name "/ROW15") (class "Default")
      (node (ref "LED8--8-8") (pin "7") (pinfunction "7_7") (pintype "passive"))
      (node (ref "LED8-8-5") (pin "7") (pinfunction "7_7") (pintype "passive"))
      (node (ref "LED8-8-6") (pin "7") (pinfunction "7_7") (pintype "passive"))
      (node (ref "LED8-8-7") (pin "7") (pinfunction "7_7") (pintype "passive"))
      (node (ref "U2") (pin "1") (pinfunction "QB_1") (pintype "tri_state"))
    )
    (net (code "57") (name "/ROW16") (class "Default")
      (node (ref "LED8--8-8") (pin "8") (pinfunction "8_8") (pintype "passive"))
      (node (ref "LED8-8-5") (pin "8") (pinfunction "8_8") (pintype "passive"))
      (node (ref "LED8-8-6") (pin "8") (pinfunction "8_8") (pintype "passive"))
      (node (ref "LED8-8-7") (pin "8") (pinfunction "8_8") (pintype "passive"))
      (node (ref "U2") (pin "15") (pinfunction "QA_15") (pintype "tri_state"))
    )
    (net (code "58") (name "/ROW17") (class "Default")
      (node (ref "LED8-8-10") (pin "1") (pinfunction "1_1") (pintype "passive"))
      (node (ref "LED8-8-11") (pin "1") (pinfunction "1_1") (pintype "passive"))
      (node (ref "LED8-8-12") (pin "1") (pinfunction "1_1") (pintype "passive"))
      (node (ref "LED8-8-9") (pin "1") (pinfunction "1_1") (pintype "passive"))
      (node (ref "U3") (pin "7") (pinfunction "QH_7") (pintype "tri_state"))
    )
    (net (code "59") (name "/ROW18") (class "Default")
      (node (ref "LED8-8-10") (pin "2") (pinfunction "2_2") (pintype "passive"))
      (node (ref "LED8-8-11") (pin "2") (pinfunction "2_2") (pintype "passive"))
      (node (ref "LED8-8-12") (pin "2") (pinfunction "2_2") (pintype "passive"))
      (node (ref "LED8-8-9") (pin "2") (pinfunction "2_2") (pintype "passive"))
      (node (ref "U3") (pin "6") (pinfunction "QG_6") (pintype "tri_state"))
    )
    (net (code "60") (name "/ROW19") (class "Default")
      (node (ref "LED8-8-10") (pin "3") (pinfunction "3_3") (pintype "passive"))
      (node (ref "LED8-8-11") (pin "3") (pinfunction "3_3") (pintype "passive"))
      (node (ref "LED8-8-12") (pin "3") (pinfunction "3_3") (pintype "passive"))
      (node (ref "LED8-8-9") (pin "3") (pinfunction "3_3") (pintype "passive"))
      (node (ref "U3") (pin "5") (pinfunction "QF_5") (pintype "tri_state"))
    )
    (net (code "61") (name "/ROW20") (class "Default")
      (node (ref "LED8-8-10") (pin "4") (pinfunction "4_4") (pintype "passive"))
      (node (ref "LED8-8-11") (pin "4") (pinfunction "4_4") (pintype "passive"))
      (node (ref "LED8-8-12") (pin "4") (pinfunction "4_4") (pintype "passive"))
      (node (ref "LED8-8-9") (pin "4") (pinfunction "4_4") (pintype "passive"))
      (node (ref "U3") (pin "4") (pinfunction "QE_4") (pintype "tri_state"))
    )
    (net (code "62") (name "/ROW21") (class "Default")
      (node (ref "LED8-8-10") (pin "5") (pinfunction "5_5") (pintype "passive"))
      (node (ref "LED8-8-11") (pin "5") (pinfunction "5_5") (pintype "passive"))
      (node (ref "LED8-8-12") (pin "5") (pinfunction "5_5") (pintype "passive"))
      (node (ref "LED8-8-9") (pin "5") (pinfunction "5_5") (pintype "passive"))
      (node (ref "U3") (pin "3") (pinfunction "QD_3") (pintype "tri_state"))
    )
    (net (code "63") (name "/ROW22") (class "Default")
      (node (ref "LED8-8-10") (pin "6") (pinfunction "6_6") (pintype "passive"))
      (node (ref "LED8-8-11") (pin "6") (pinfunction "6_6") (pintype "passive"))
      (node (ref "LED8-8-12") (pin "6") (pinfunction "6_6") (pintype "passive"))
      (node (ref "LED8-8-9") (pin "6") (pinfunction "6_6") (pintype "passive"))
      (node (ref "U3") (pin "2") (pinfunction "QC_2") (pintype "tri_state"))
    )
    (net (code "64") (name "/ROW23") (class "Default")
      (node (ref "LED8-8-10") (pin "7") (pinfunction "7_7") (pintype "passive"))
      (node (ref "LED8-8-11") (pin "7") (pinfunction "7_7") (pintype "passive"))
      (node (ref "LED8-8-12") (pin "7") (pinfunction "7_7") (pintype "passive"))
      (node (ref "LED8-8-9") (pin "7") (pinfunction "7_7") (pintype "passive"))
      (node (ref "U3") (pin "1") (pinfunction "QB_1") (pintype "tri_state"))
    )
    (net (code "65") (name "/ROW24") (class "Default")
      (node (ref "LED8-8-10") (pin "8") (pinfunction "8_8") (pintype "passive"))
      (node (ref "LED8-8-11") (pin "8") (pinfunction "8_8") (pintype "passive"))
      (node (ref "LED8-8-12") (pin "8") (pinfunction "8_8") (pintype "passive"))
      (node (ref "LED8-8-9") (pin "8") (pinfunction "8_8") (pintype "passive"))
      (node (ref "U3") (pin "15") (pinfunction "QA_15") (pintype "tri_state"))
    )
    (net (code "66") (name "/ROW25") (class "Default")
      (node (ref "LED8-8-13") (pin "1") (pinfunction "1_1") (pintype "passive"))
      (node (ref "LED8-8-14") (pin "1") (pinfunction "1_1") (pintype "passive"))
      (node (ref "LED8-8-15") (pin "1") (pinfunction "1_1") (pintype "passive"))
      (node (ref "LED8-8-16") (pin "1") (pinfunction "1_1") (pintype "passive"))
      (node (ref "U4") (pin "7") (pinfunction "QH_7") (pintype "tri_state"))
    )
    (net (code "67") (name "/ROW26") (class "Default")
      (node (ref "LED8-8-13") (pin "2") (pinfunction "2_2") (pintype "passive"))
      (node (ref "LED8-8-14") (pin "2") (pinfunction "2_2") (pintype "passive"))
      (node (ref "LED8-8-15") (pin "2") (pinfunction "2_2") (pintype "passive"))
      (node (ref "LED8-8-16") (pin "2") (pinfunction "2_2") (pintype "passive"))
      (node (ref "U4") (pin "6") (pinfunction "QG_6") (pintype "tri_state"))
    )
    (net (code "68") (name "/ROW27") (class "Default")
      (node (ref "LED8-8-13") (pin "3") (pinfunction "3_3") (pintype "passive"))
      (node (ref "LED8-8-14") (pin "3") (pinfunction "3_3") (pintype "passive"))
      (node (ref "LED8-8-15") (pin "3") (pinfunction "3_3") (pintype "passive"))
      (node (ref "LED8-8-16") (pin "3") (pinfunction "3_3") (pintype "passive"))
      (node (ref "U4") (pin "5") (pinfunction "QF_5") (pintype "tri_state"))
    )
    (net (code "69") (name "/ROW28") (class "Default")
      (node (ref "LED8-8-13") (pin "4") (pinfunction "4_4") (pintype "passive"))
      (node (ref "LED8-8-14") (pin "4") (pinfunction "4_4") (pintype "passive"))
      (node (ref "LED8-8-15") (pin "4") (pinfunction "4_4") (pintype "passive"))
      (node (ref "LED8-8-16") (pin "4") (pinfunction "4_4") (pintype "passive"))
      (node (ref "U4") (pin "4") (pinfunction "QE_4") (pintype "tri_state"))
    )
    (net (code "70") (name "/ROW29") (class "Default")
      (node (ref "LED8-8-13") (pin "5") (pinfunction "5_5") (pintype "passive"))
      (node (ref "LED8-8-14") (pin "5") (pinfunction "5_5") (pintype "passive"))
      (node (ref "LED8-8-15") (pin "5") (pinfunction "5_5") (pintype "passive"))
      (node (ref "LED8-8-16") (pin "5") (pinfunction "5_5") (pintype "passive"))
      (node (ref "U4") (pin "3") (pinfunction "QD_3") (pintype "tri_state"))
    )
    (net (code "71") (name "/ROW30") (class "Default")
      (node (ref "LED8-8-13") (pin "6") (pinfunction "6_6") (pintype "passive"))
      (node (ref "LED8-8-14") (pin "6") (pinfunction "6_6") (pintype "passive"))
      (node (ref "LED8-8-15") (pin "6") (pinfunction "6_6") (pintype "passive"))
      (node (ref "LED8-8-16") (pin "6") (pinfunction "6_6") (pintype "passive"))
      (node (ref "U4") (pin "2") (pinfunction "QC_2") (pintype "tri_state"))
    )
    (net (code "72") (name "/ROW31") (class "Default")
      (node (ref "LED8-8-13") (pin "7") (pinfunction "7_7") (pintype "passive"))
      (node (ref "LED8-8-14") (pin "7") (pinfunction "7_7") (pintype "passive"))
      (node (ref "LED8-8-15") (pin "7") (pinfunction "7_7") (pintype "passive"))
      (node (ref "LED8-8-16") (pin "7") (pinfunction "7_7") (pintype "passive"))
      (node (ref "U4") (pin "1") (pinfunction "QB_1") (pintype "tri_state"))
    )
    (net (code "73") (name "/ROW32") (class "Default")
      (node (ref "LED8-8-13") (pin "8") (pinfunction "8_8") (pintype "passive"))
      (node (ref "LED8-8-14") (pin "8") (pinfunction "8_8") (pintype "passive"))
      (node (ref "LED8-8-15") (pin "8") (pinfunction "8_8") (pintype "passive"))
      (node (ref "LED8-8-16") (pin "8") (pinfunction "8_8") (pintype "passive"))
      (node (ref "U4") (pin "15") (pinfunction "QA_15") (pintype "tri_state"))
    )
    (net (code "74") (name "/ROWBUTTON") (class "Default")
      (node (ref "S-ROW") (pin "2") (pinfunction "2_2") (pintype "passive"))
      (node (ref "SCM") (pin "13") (pinfunction "P3.6/~{INT2}/RxD_2/CCP1_2_13") (pintype "passive"))
    )
    (net (code "75") (name "/ROWD") (class "Default")
      (node (ref "SCM") (pin "11") (pinfunction "P3.2/INT0_11") (pintype "passive"))
      (node (ref "U1") (pin "14") (pinfunction "SER_14") (pintype "input"))
    )
    (net (code "76") (name "/SHCP") (class "Default")
      (node (ref "SCM") (pin "9") (pinfunction "P3.0/RxD/~{INT4}/T2CLKO_9") (pintype "passive"))
      (node (ref "U1") (pin "11") (pinfunction "SRCLK_11") (pintype "input"))
      (node (ref "U2") (pin "11") (pinfunction "SRCLK_11") (pintype "input"))
      (node (ref "U3") (pin "11") (pinfunction "SRCLK_11") (pintype "input"))
      (node (ref "U4") (pin "11") (pinfunction "SRCLK_11") (pintype "input"))
      (node (ref "U5") (pin "11") (pinfunction "SRCLK_11") (pintype "input"))
      (node (ref "U6") (pin "11") (pinfunction "SRCLK_11") (pintype "input"))
      (node (ref "U7") (pin "11") (pinfunction "SRCLK_11") (pintype "input"))
      (node (ref "U8") (pin "11") (pinfunction "SRCLK_11") (pintype "input"))
    )
    (net (code "77") (name "/STCP") (class "Default")
      (node (ref "SCM") (pin "10") (pinfunction "P3.1/TxD/T2_10") (pintype "passive"))
      (node (ref "U1") (pin "12") (pinfunction "RCLK_12") (pintype "input"))
      (node (ref "U2") (pin "12") (pinfunction "RCLK_12") (pintype "input"))
      (node (ref "U3") (pin "12") (pinfunction "RCLK_12") (pintype "input"))
      (node (ref "U4") (pin "12") (pinfunction "RCLK_12") (pintype "input"))
      (node (ref "U5") (pin "12") (pinfunction "RCLK_12") (pintype "input"))
      (node (ref "U6") (pin "12") (pinfunction "RCLK_12") (pintype "input"))
      (node (ref "U7") (pin "12") (pinfunction "RCLK_12") (pintype "input"))
      (node (ref "U8") (pin "12") (pinfunction "RCLK_12") (pintype "input"))
    )
    (net (code "78") (name "/V3-1") (class "Default")
      (node (ref "1117-1") (pin "2") (pinfunction "OUT_2") (pintype "passive"))
      (node (ref "C4") (pin "1") (pinfunction "1_1") (pintype "passive"))
      (node (ref "U5") (pin "10") (pinfunction "~{SRCLR}_10") (pintype "input"))
      (node (ref "U5") (pin "16") (pinfunction "VCC_16") (pintype "power_in"))
      (node (ref "U6") (pin "10") (pinfunction "~{SRCLR}_10") (pintype "input"))
      (node (ref "U6") (pin "16") (pinfunction "VCC_16") (pintype "power_in"))
      (node (ref "U7") (pin "10") (pinfunction "~{SRCLR}_10") (pintype "input"))
      (node (ref "U7") (pin "16") (pinfunction "VCC_16") (pintype "power_in"))
      (node (ref "U8") (pin "10") (pinfunction "~{SRCLR}_10") (pintype "input"))
      (node (ref "U8") (pin "16") (pinfunction "VCC_16") (pintype "power_in"))
    )
    (net (code "79") (name "/V3-2") (class "Default")
      (node (ref "1117-2") (pin "2") (pinfunction "OUT_2") (pintype "passive"))
      (node (ref "C5") (pin "1") (pinfunction "1_1") (pintype "passive"))
      (node (ref "U1") (pin "10") (pinfunction "~{SRCLR}_10") (pintype "input"))
      (node (ref "U1") (pin "16") (pinfunction "VCC_16") (pintype "power_in"))
    )
    (net (code "80") (name "/V3-3") (class "Default")
      (node (ref "1117-3") (pin "2") (pinfunction "OUT_2") (pintype "passive"))
      (node (ref "C6") (pin "1") (pinfunction "1_1") (pintype "passive"))
      (node (ref "U2") (pin "10") (pinfunction "~{SRCLR}_10") (pintype "input"))
      (node (ref "U2") (pin "16") (pinfunction "VCC_16") (pintype "power_in"))
    )
    (net (code "81") (name "/V3-4") (class "Default")
      (node (ref "1117-4") (pin "2") (pinfunction "OUT_2") (pintype "passive"))
      (node (ref "C7") (pin "1") (pinfunction "1_1") (pintype "passive"))
      (node (ref "U3") (pin "10") (pinfunction "~{SRCLR}_10") (pintype "input"))
      (node (ref "U3") (pin "16") (pinfunction "VCC_16") (pintype "power_in"))
    )
    (net (code "82") (name "/V3-5") (class "Default")
      (node (ref "1117-5") (pin "2") (pinfunction "OUT_2") (pintype "passive"))
      (node (ref "C8") (pin "1") (pinfunction "1_1") (pintype "passive"))
      (node (ref "U4") (pin "10") (pinfunction "~{SRCLR}_10") (pintype "input"))
      (node (ref "U4") (pin "16") (pinfunction "VCC_16") (pintype "power_in"))
    )
    (net (code "83") (name "/VCC") (class "Default")
      (node (ref "1117-1") (pin "3") (pinfunction "IN_3") (pintype "passive"))
      (node (ref "1117-2") (pin "3") (pinfunction "IN_3") (pintype "passive"))
      (node (ref "1117-3") (pin "3") (pinfunction "IN_3") (pintype "passive"))
      (node (ref "1117-4") (pin "3") (pinfunction "IN_3") (pintype "passive"))
      (node (ref "1117-5") (pin "3") (pinfunction "IN_3") (pintype "passive"))
      (node (ref "C3") (pin "1") (pinfunction "1_1") (pintype "passive"))
      (node (ref "DC005") (pin "1") (pinfunction "VCC_1") (pintype "passive"))
      (node (ref "SCM") (pin "6") (pinfunction "Vcc_6") (pintype "passive"))
      (node (ref "UCLOCK") (pin "1") (pinfunction "VCC2_1") (pintype "power_in"))
      (node (ref "UCLOCK") (pin "8") (pinfunction "VCC1_8") (pintype "power_in"))
    )
    (net (code "84") (name "Net-(R1-Pad2)") (class "Default")
      (node (ref "R1") (pin "2") (pinfunction "2_2") (pintype "passive"))
      (node (ref "S-COL") (pin "1") (pinfunction "1_1") (pintype "passive"))
    )
    (net (code "85") (name "Net-(R2-Pad2)") (class "Default")
      (node (ref "R2") (pin "2") (pinfunction "2_2") (pintype "passive"))
      (node (ref "S-ROW") (pin "1") (pinfunction "1_1") (pintype "passive"))
    )
    (net (code "86") (name "Net-(U1-QH')") (class "Default")
      (node (ref "U1") (pin "9") (pinfunction "QH'_9") (pintype "output"))
      (node (ref "U2") (pin "14") (pinfunction "SER_14") (pintype "input"))
    )
    (net (code "87") (name "Net-(U2-QH')") (class "Default")
      (node (ref "U2") (pin "9") (pinfunction "QH'_9") (pintype "output"))
      (node (ref "U3") (pin "14") (pinfunction "SER_14") (pintype "input"))
    )
    (net (code "88") (name "Net-(U3-QH')") (class "Default")
      (node (ref "U3") (pin "9") (pinfunction "QH'_9") (pintype "output"))
      (node (ref "U4") (pin "14") (pinfunction "SER_14") (pintype "input"))
    )
    (net (code "89") (name "Net-(U5-QH')") (class "Default")
      (node (ref "U5") (pin "9") (pinfunction "QH'_9") (pintype "output"))
      (node (ref "U6") (pin "14") (pinfunction "SER_14") (pintype "input"))
    )
    (net (code "90") (name "Net-(U6-QH')") (class "Default")
      (node (ref "U6") (pin "9") (pinfunction "QH'_9") (pintype "output"))
      (node (ref "U7") (pin "14") (pinfunction "SER_14") (pintype "input"))
    )
    (net (code "91") (name "Net-(U7-QH')") (class "Default")
      (node (ref "U7") (pin "9") (pinfunction "QH'_9") (pintype "output"))
      (node (ref "U8") (pin "14") (pinfunction "SER_14") (pintype "input"))
    )
    (net (code "92") (name "Net-(UCLOCK-X1)") (class "Default")
      (node (ref "C1") (pin "2") (pinfunction "2_2") (pintype "passive"))
      (node (ref "UCLOCK") (pin "2") (pinfunction "X1_2") (pintype "input"))
      (node (ref "Y1") (pin "2") (pinfunction "OSC2_2") (pintype "passive"))
    )
    (net (code "93") (name "Net-(UCLOCK-X2)") (class "Default")
      (node (ref "C2") (pin "2") (pinfunction "2_2") (pintype "passive"))
      (node (ref "UCLOCK") (pin "3") (pinfunction "X2_3") (pintype "input"))
      (node (ref "Y1") (pin "1") (pinfunction "OSC1_1") (pintype "passive"))
    )
    (net (code "94") (name "unconnected-(SCM-P1.0{slash}ADC0{slash}CCP1-Pad15)") (class "Default")
      (node (ref "SCM") (pin "15") (pinfunction "P1.0/ADC0/CCP1_15") (pintype "passive"))
    )
    (net (code "95") (name "unconnected-(SCM-P1.1{slash}ADC1{slash}CCP0-Pad16)") (class "Default")
      (node (ref "SCM") (pin "16") (pinfunction "P1.1/ADC1/CCP0_16") (pintype "passive"))
    )
    (net (code "96") (name "unconnected-(SCM-P1.5{slash}ADC5{slash}SCLK-Pad4)") (class "Default")
      (node (ref "SCM") (pin "4") (pinfunction "P1.5/ADC5/SCLK_4") (pintype "passive"))
    )
    (net (code "97") (name "unconnected-(SCM-P5.4{slash}RST{slash}MCLKO{slash}CMP--Pad5)") (class "Default")
      (node (ref "SCM") (pin "5") (pinfunction "P5.4/RST/MCLKO/CMP-_5") (pintype "passive"))
    )
    (net (code "98") (name "unconnected-(SCM-P5.5{slash}CMP+-Pad7)") (class "Default")
      (node (ref "SCM") (pin "7") (pinfunction "P5.5/CMP+_7") (pintype "passive"))
    )
    (net (code "99") (name "unconnected-(U4-QH'-Pad9)") (class "Default")
      (node (ref "U4") (pin "9") (pinfunction "QH'_9") (pintype "output"))
    )
    (net (code "100") (name "unconnected-(U8-QH'-Pad9)") (class "Default")
      (node (ref "U8") (pin "9") (pinfunction "QH'_9") (pintype "output"))
    )
  )
)
